# ADSR_Schematic.net
KiCad netlist of a schematic drawn in Altium Designer
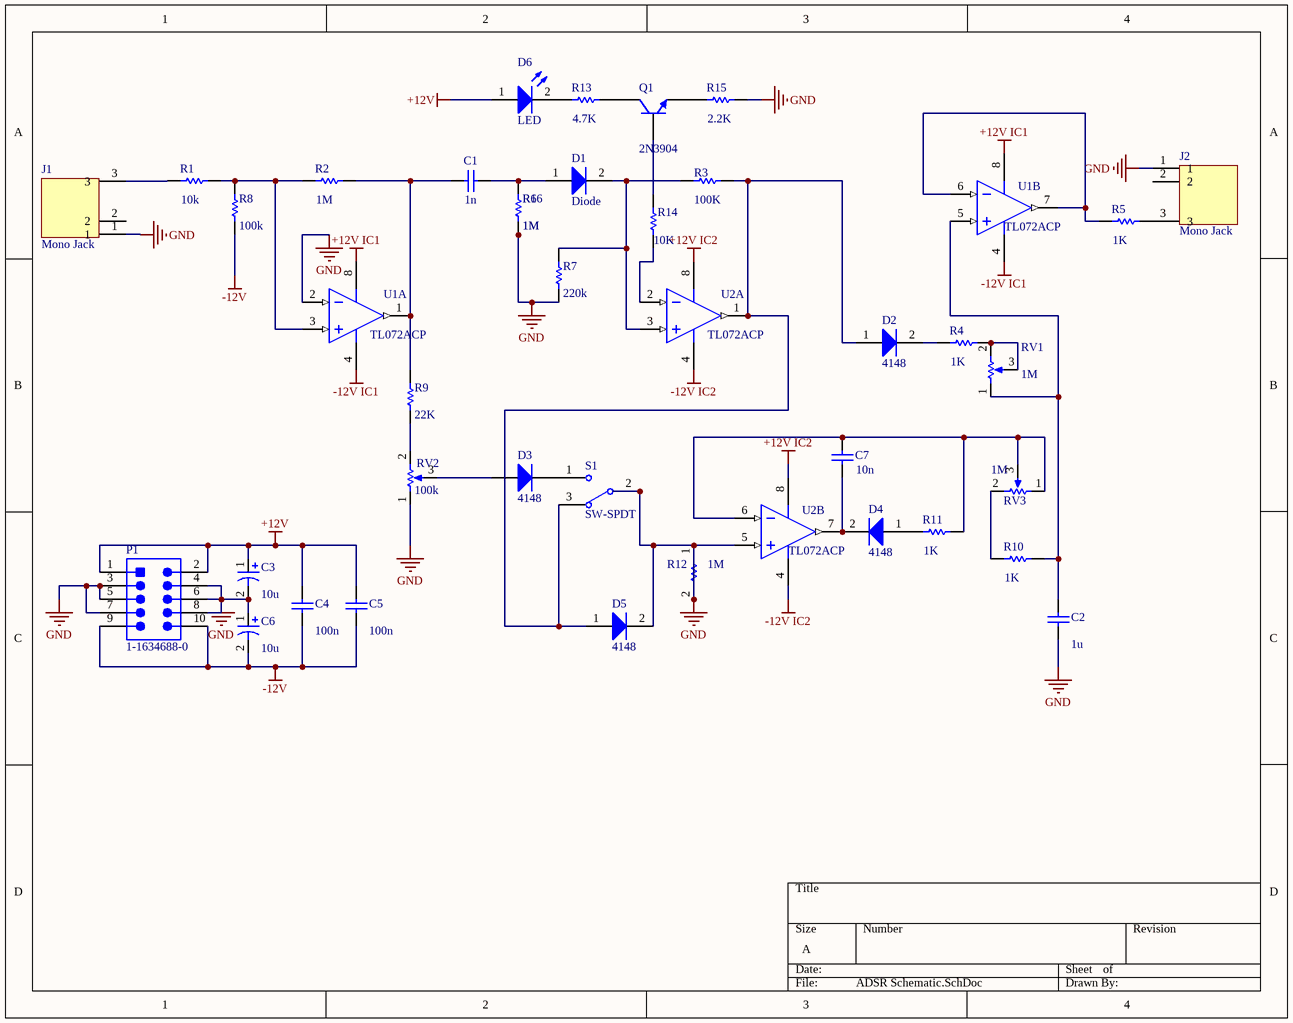
[diagram p0: ADSR Schematic.SchDoc]

(export (version "E")
  (design (tool "Eeschema 10.0.6"))
  (components
    (comp (ref "C1")
      (value "1n")
      (footprint "Ceramic_Cap")
      (description "Capacitor")
      (fields (field (name "Comment") "Cap") (field (name "PUBLISHER") "Altium Limited"))
      (libsource (lib "Miscellaneous Devices") (part "Cap"))
    )
    (comp (ref "C2")
      (value "1u")
      (footprint "Ceramic_Cap")
      (description "Capacitor")
      (fields (field (name "Comment") "Cap") (field (name "PUBLISHER") "Altium Limited"))
      (libsource (lib "Miscellaneous Devices") (part "Cap"))
    )
    (comp (ref "C3")
      (value "10u")
      (footprint "Electrolytic_Cap")
      (description "Polarized Capacitor (Radial)")
      (fields (field (name "Comment") "Cap Pol1") (field (name "PUBLISHER") "Altium Limited"))
      (libsource (lib "Miscellaneous Devices") (part "Cap Pol1"))
    )
    (comp (ref "C4")
      (value "100n")
      (footprint "Ceramic_Cap")
      (description "Capacitor")
      (fields (field (name "Comment") "Cap") (field (name "PUBLISHER") "Altium Limited"))
      (libsource (lib "Miscellaneous Devices") (part "Cap"))
    )
    (comp (ref "C5")
      (value "100n")
      (footprint "Ceramic_Cap")
      (description "Capacitor")
      (fields (field (name "Comment") "Cap") (field (name "PUBLISHER") "Altium Limited"))
      (libsource (lib "Miscellaneous Devices") (part "Cap"))
    )
    (comp (ref "C6")
      (value "10u")
      (footprint "Electrolytic_Cap")
      (description "Polarized Capacitor (Radial)")
      (fields (field (name "Comment") "Cap Pol1") (field (name "PUBLISHER") "Altium Limited"))
      (libsource (lib "Miscellaneous Devices") (part "Cap Pol1"))
    )
    (comp (ref "C7")
      (value "10n")
      (footprint "Ceramic_Cap")
      (description "Capacitor")
      (fields (field (name "Comment") "Cap") (field (name "PUBLISHER") "Altium Limited"))
      (libsource (lib "Miscellaneous Devices") (part "Cap"))
    )
    (comp (ref "D1")
      (value "Diode")
      (footprint "DIODE")
      (description "Default Diode")
      (fields (field (name "PUBLISHER") "Altium Limited"))
      (libsource (lib "Miscellaneous Devices") (part "Diode"))
    )
    (comp (ref "D2")
      (value "4148")
      (footprint "DIODE")
      (description "Default Diode")
      (fields (field (name "PUBLISHER") "Altium Limited"))
      (libsource (lib "Miscellaneous Devices") (part "Diode"))
    )
    (comp (ref "D3")
      (value "4148")
      (footprint "DIODE")
      (description "Default Diode")
      (fields (field (name "PUBLISHER") "Altium Limited"))
      (libsource (lib "") (part "Diode_1"))
    )
    (comp (ref "D4")
      (value "4148")
      (footprint "DIODE")
      (description "Default Diode")
      (fields (field (name "PUBLISHER") "Altium Limited"))
      (libsource (lib "Miscellaneous Devices") (part "Diode"))
    )
    (comp (ref "D5")
      (value "4148")
      (footprint "DIODE")
      (description "Default Diode")
      (fields (field (name "PUBLISHER") "Altium Limited"))
      (libsource (lib "Miscellaneous Devices") (part "Diode"))
    )
    (comp (ref "D6")
      (value "LED")
      (footprint "DIODE")
      (description "Typical INFRARED GaAs LED")
      (fields (field (name "PUBLISHER") "Altium Limited"))
      (libsource (lib "Miscellaneous Devices") (part "LED0"))
    )
    (comp (ref "J1")
      (value "Mono Jack")
      (footprint "MONO_Jack")
      (description "Phone Connectors Audio Socket 3.5MM 2P SCR")
      (fields (field (name "MANUFACTURER") "Schurter") (field (name "MANUFACTURER PART NUMBER") "4832.2211"))
      (libsource (lib "Schlib1") (part "4832.2211"))
    )
    (comp (ref "J2")
      (value "Mono Jack")
      (footprint "MONO_Jack")
      (description "Phone Connectors Audio Socket 3.5MM 2P SCR")
      (fields (field (name "MANUFACTURER") "Schurter") (field (name "MANUFACTURER PART NUMBER") "4832.2211"))
      (libsource (lib "") (part "4832.2211_1"))
    )
    (comp (ref "P1")
      (value "1-1634688-0")
      (footprint "TECO-1-1634688-0-10_V")
      (fields (field (name "MANUFACTURER") "TE Connectivity"))
      (libsource (lib "Altium Content Vault") (part "CN-2P-M-R10"))
    )
    (comp (ref "Q1")
      (value "2N3904")
      (footprint "TO-92A")
      (description "NPN General Purpose Amplifier")
      (fields (field (name "PUBLISHER") "Altium Limited"))
      (libsource (lib "Miscellaneous Devices") (part "2N3904"))
    )
    (comp (ref "R1")
      (value "10k")
      (footprint "R_SMT")
      (description "Resistor")
      (fields (field (name "Comment") "Res1") (field (name "PUBLISHER") "Altium Limited"))
      (libsource (lib "Miscellaneous Devices") (part "Res1"))
    )
    (comp (ref "R2")
      (value "1M")
      (footprint "R_SMT")
      (description "Resistor")
      (fields (field (name "Comment") "Res1") (field (name "PUBLISHER") "Altium Limited"))
      (libsource (lib "Miscellaneous Devices") (part "Res1"))
    )
    (comp (ref "R3")
      (value "100K")
      (footprint "R_SMT")
      (description "Resistor")
      (fields (field (name "Comment") "Res1") (field (name "PUBLISHER") "Altium Limited"))
      (libsource (lib "Miscellaneous Devices") (part "Res1"))
    )
    (comp (ref "R4")
      (value "1K")
      (footprint "R_SMT")
      (description "Resistor")
      (fields (field (name "Comment") "Res1") (field (name "PUBLISHER") "Altium Limited"))
      (libsource (lib "Miscellaneous Devices") (part "Res1"))
    )
    (comp (ref "R5")
      (value "1K")
      (footprint "R_SMT")
      (description "Resistor")
      (fields (field (name "Comment") "Res1") (field (name "PUBLISHER") "Altium Limited"))
      (libsource (lib "Miscellaneous Devices") (part "Res1"))
    )
    (comp (ref "R6")
      (value "1M")
      (footprint "AXIAL-0.3")
      (description "Resistor")
      (fields (field (name "Comment") "Res1") (field (name "PUBLISHER") "Altium Limited"))
      (libsource (lib "Miscellaneous Devices") (part "Res1"))
    )
    (comp (ref "R7")
      (value "220k")
      (footprint "R_SMT")
      (description "Resistor")
      (fields (field (name "Comment") "Res1") (field (name "PUBLISHER") "Altium Limited"))
      (libsource (lib "Miscellaneous Devices") (part "Res1"))
    )
    (comp (ref "R8")
      (value "100k")
      (footprint "R_SMT")
      (description "Resistor")
      (fields (field (name "Comment") "Res1") (field (name "PUBLISHER") "Altium Limited"))
      (libsource (lib "Miscellaneous Devices") (part "Res1"))
    )
    (comp (ref "R9")
      (value "22K")
      (footprint "R_SMT")
      (description "Resistor")
      (fields (field (name "Comment") "Res1") (field (name "PUBLISHER") "Altium Limited"))
      (libsource (lib "Miscellaneous Devices") (part "Res1"))
    )
    (comp (ref "R10")
      (value "1K")
      (footprint "R_SMT")
      (description "Resistor")
      (fields (field (name "Comment") "Res1") (field (name "PUBLISHER") "Altium Limited"))
      (libsource (lib "Miscellaneous Devices") (part "Res1"))
    )
    (comp (ref "R11")
      (value "1K")
      (footprint "R_SMT")
      (description "Resistor")
      (fields (field (name "Comment") "Res1") (field (name "PUBLISHER") "Altium Limited"))
      (libsource (lib "Miscellaneous Devices") (part "Res1"))
    )
    (comp (ref "R12")
      (value "1M")
      (footprint "R_SMT")
      (description "Resistor")
      (fields (field (name "Comment") "Res1") (field (name "PUBLISHER") "Altium Limited"))
      (libsource (lib "") (part "Res1_1"))
    )
    (comp (ref "R13")
      (value "4.7K")
      (footprint "R_SMT")
      (description "Resistor")
      (fields (field (name "Comment") "Res1") (field (name "PUBLISHER") "Altium Limited"))
      (libsource (lib "Miscellaneous Devices") (part "Res1"))
    )
    (comp (ref "R14")
      (value "10K")
      (footprint "R_SMT")
      (description "Resistor")
      (fields (field (name "Comment") "Res1") (field (name "PUBLISHER") "Altium Limited"))
      (libsource (lib "Miscellaneous Devices") (part "Res1"))
    )
    (comp (ref "R15")
      (value "2.2K")
      (footprint "R_SMT")
      (description "Resistor")
      (fields (field (name "Comment") "Res1") (field (name "PUBLISHER") "Altium Limited"))
      (libsource (lib "Miscellaneous Devices") (part "Res1"))
    )
    (comp (ref "R16")
      (value "1M")
      (footprint "R_SMT")
      (description "Resistor")
      (fields (field (name "Comment") "Res1") (field (name "PUBLISHER") "Altium Limited"))
      (libsource (lib "Miscellaneous Devices") (part "Res1"))
    )
    (comp (ref "RV1")
      (value "1M")
      (footprint "POT")
      (description "Potentiometer")
      (fields (field (name "Comment") "RPot") (field (name "PUBLISHER") "Altium Limited"))
      (libsource (lib "Miscellaneous Devices") (part "RPot"))
    )
    (comp (ref "RV2")
      (value "100k")
      (footprint "POT")
      (description "Potentiometer")
      (fields (field (name "Comment") "RPot") (field (name "PUBLISHER") "Altium Limited"))
      (libsource (lib "Miscellaneous Devices") (part "RPot"))
    )
    (comp (ref "RV3")
      (value "1M")
      (footprint "POT")
      (description "Potentiometer")
      (fields (field (name "Comment") "RPot") (field (name "PUBLISHER") "Altium Limited"))
      (libsource (lib "Miscellaneous Devices") (part "RPot"))
    )
    (comp (ref "S1")
      (value "SW-SPDT")
      (footprint "TL36WW15050")
      (description "SPDT Subminiature Toggle Switch, Right Angle Mounting, Vertical Actuation")
      (fields (field (name "PUBLISHER") "Altium Limited"))
      (libsource (lib "Miscellaneous Devices") (part "SW-SPDT"))
    )
    (comp (ref "U1")
      (value "TL072ACP")
      (footprint "P0008A")
      (fields (field (name "MANUFACTURER") "Texas Instruments"))
      (libsource (lib "Schlib1") (part "TI-AMP-D6-2-8_D"))
    )
    (comp (ref "U2")
      (value "TL072ACP")
      (footprint "P0008A")
      (fields (field (name "MANUFACTURER") "Texas Instruments"))
      (libsource (lib "Altium Content Vault") (part "TI-AMP-D6-2-8_D"))
    )
  )
  (nets
    (net (code "1") (name "+12V") (class "Default")
      (node (ref "C3") (pin "1") (pinfunction "1_1") (pintype "passive"))
      (node (ref "C4") (pin "1") (pinfunction "1_1") (pintype "passive"))
      (node (ref "C5") (pin "1") (pinfunction "1_1") (pintype "passive"))
      (node (ref "D6") (pin "1") (pinfunction "A_1") (pintype "passive"))
      (node (ref "P1") (pin "1") (pinfunction "1_1") (pintype "passive"))
      (node (ref "P1") (pin "2") (pinfunction "2_2") (pintype "passive"))
    )
    (net (code "2") (name "+12V IC1") (class "Default")
      (node (ref "U1") (pin "8") (pinfunction "VCC+_8") (pintype "power_in"))
    )
    (net (code "3") (name "+12V IC2") (class "Default")
      (node (ref "U2") (pin "8") (pinfunction "VCC+_8") (pintype "power_in"))
    )
    (net (code "4") (name "-12V") (class "Default")
      (node (ref "C4") (pin "2") (pinfunction "2_2") (pintype "passive"))
      (node (ref "C5") (pin "2") (pinfunction "2_2") (pintype "passive"))
      (node (ref "C6") (pin "2") (pinfunction "2_2") (pintype "passive"))
      (node (ref "P1") (pin "10") (pinfunction "10_10") (pintype "passive"))
      (node (ref "P1") (pin "9") (pinfunction "9_9") (pintype "passive"))
      (node (ref "R8") (pin "1") (pinfunction "1_1") (pintype "passive"))
    )
    (net (code "5") (name "-12V IC1") (class "Default")
      (node (ref "U1") (pin "4") (pinfunction "VCC-_4") (pintype "power_in"))
    )
    (net (code "6") (name "-12V IC2") (class "Default")
      (node (ref "U2") (pin "4") (pinfunction "VCC-_4") (pintype "power_in"))
    )
    (net (code "7") (name "GND") (class "Default")
      (node (ref "C2") (pin "2") (pinfunction "2_2") (pintype "passive"))
      (node (ref "C3") (pin "2") (pinfunction "2_2") (pintype "passive"))
      (node (ref "C6") (pin "1") (pinfunction "1_1") (pintype "passive"))
      (node (ref "D5") (pin "2") (pinfunction "K_2") (pintype "passive"))
      (node (ref "J1") (pin "1") (pinfunction "1_1") (pintype "passive"))
      (node (ref "J2") (pin "1") (pinfunction "1_1") (pintype "passive"))
      (node (ref "P1") (pin "3") (pinfunction "3_3") (pintype "passive"))
      (node (ref "P1") (pin "4") (pinfunction "4_4") (pintype "passive"))
      (node (ref "P1") (pin "5") (pinfunction "5_5") (pintype "passive"))
      (node (ref "P1") (pin "6") (pinfunction "6_6") (pintype "passive"))
      (node (ref "P1") (pin "7") (pinfunction "7_7") (pintype "passive"))
      (node (ref "P1") (pin "8") (pinfunction "8_8") (pintype "passive"))
      (node (ref "R12") (pin "1") (pinfunction "1_1") (pintype "passive"))
      (node (ref "R12") (pin "2") (pinfunction "2_2") (pintype "passive"))
      (node (ref "R15") (pin "2") (pinfunction "2_2") (pintype "passive"))
      (node (ref "R16") (pin "2") (pinfunction "2_2") (pintype "passive"))
      (node (ref "R6") (pin "2") (pinfunction "2_2") (pintype "passive"))
      (node (ref "R7") (pin "1") (pinfunction "1_1") (pintype "passive"))
      (node (ref "RV2") (pin "1") (pinfunction "TOP_1") (pintype "passive"))
      (node (ref "S1") (pin "2") (pinfunction "2_2") (pintype "passive"))
      (node (ref "U1") (pin "2") (pinfunction "IN1-_2") (pintype "input"))
      (node (ref "U2") (pin "5") (pinfunction "IN2+_5") (pintype "input"))
    )
    (net (code "8") (name "Net-(D1-A)") (class "Default")
      (node (ref "C1") (pin "2") (pinfunction "2_2") (pintype "passive"))
      (node (ref "D1") (pin "1") (pinfunction "A_1") (pintype "passive"))
      (node (ref "R16") (pin "1") (pinfunction "1_1") (pintype "passive"))
      (node (ref "R6") (pin "1") (pinfunction "1_1") (pintype "passive"))
    )
    (net (code "9") (name "Net-(D1-K)") (class "Default")
      (node (ref "D1") (pin "2") (pinfunction "K_2") (pintype "passive"))
      (node (ref "R3") (pin "2") (pinfunction "2_2") (pintype "passive"))
      (node (ref "R7") (pin "2") (pinfunction "2_2") (pintype "passive"))
      (node (ref "U2") (pin "3") (pinfunction "IN1+_3") (pintype "input"))
    )
    (net (code "10") (name "Net-(D2-A)") (class "Default")
      (node (ref "D2") (pin "1") (pinfunction "A_1") (pintype "passive"))
      (node (ref "D5") (pin "1") (pinfunction "A_1") (pintype "passive"))
      (node (ref "R3") (pin "1") (pinfunction "1_1") (pintype "passive"))
      (node (ref "S1") (pin "3") (pinfunction "3_3") (pintype "passive"))
      (node (ref "U2") (pin "1") (pinfunction "OUT1_1") (pintype "output"))
    )
    (net (code "11") (name "Net-(D2-K)") (class "Default")
      (node (ref "D2") (pin "2") (pinfunction "K_2") (pintype "passive"))
      (node (ref "R4") (pin "2") (pinfunction "2_2") (pintype "passive"))
    )
    (net (code "12") (name "Net-(D3-A)") (class "Default")
      (node (ref "D3") (pin "1") (pinfunction "A_1") (pintype "passive"))
      (node (ref "RV2") (pin "3") (pinfunction "TAP_3") (pintype "passive"))
    )
    (net (code "13") (name "Net-(D3-K)") (class "Default")
      (node (ref "D3") (pin "2") (pinfunction "K_2") (pintype "passive"))
      (node (ref "S1") (pin "1") (pinfunction "1_1") (pintype "passive"))
    )
    (net (code "14") (name "Net-(D4-A)") (class "Default")
      (node (ref "D4") (pin "1") (pinfunction "A_1") (pintype "passive"))
      (node (ref "R11") (pin "1") (pinfunction "1_1") (pintype "passive"))
    )
    (net (code "15") (name "Net-(D4-K)") (class "Default")
      (node (ref "C7") (pin "1") (pinfunction "1_1") (pintype "passive"))
      (node (ref "D4") (pin "2") (pinfunction "K_2") (pintype "passive"))
      (node (ref "U2") (pin "7") (pinfunction "OUT2_7") (pintype "output"))
    )
    (net (code "16") (name "Net-(D6-K)") (class "Default")
      (node (ref "D6") (pin "2") (pinfunction "K_2") (pintype "passive"))
      (node (ref "R13") (pin "1") (pinfunction "1_1") (pintype "passive"))
    )
    (net (code "17") (name "Net-(J1-Pad3)") (class "Default")
      (node (ref "J1") (pin "3") (pinfunction "3_3") (pintype "passive"))
      (node (ref "R1") (pin "1") (pinfunction "1_1") (pintype "passive"))
    )
    (net (code "18") (name "Net-(J2-Pad3)") (class "Default")
      (node (ref "J2") (pin "3") (pinfunction "3_3") (pintype "passive"))
      (node (ref "R5") (pin "2") (pinfunction "2_2") (pintype "passive"))
    )
    (net (code "19") (name "Net-(Q1-B)") (class "Default")
      (node (ref "Q1") (pin "2") (pinfunction "B_2") (pintype "passive"))
      (node (ref "R14") (pin "1") (pinfunction "1_1") (pintype "passive"))
    )
    (net (code "20") (name "Net-(Q1-C)") (class "Default")
      (node (ref "Q1") (pin "3") (pinfunction "C_3") (pintype "passive"))
      (node (ref "R13") (pin "2") (pinfunction "2_2") (pintype "passive"))
    )
    (net (code "21") (name "Net-(Q1-E)") (class "Default")
      (node (ref "Q1") (pin "1") (pinfunction "E_1") (pintype "passive"))
      (node (ref "R15") (pin "1") (pinfunction "1_1") (pintype "passive"))
    )
    (net (code "22") (name "Net-(RV1-BOT)") (class "Default")
      (node (ref "R4") (pin "1") (pinfunction "1_1") (pintype "passive"))
      (node (ref "RV1") (pin "2") (pinfunction "BOT_2") (pintype "passive"))
      (node (ref "RV1") (pin "3") (pinfunction "TAP_3") (pintype "passive"))
    )
    (net (code "23") (name "Net-(RV1-TOP)") (class "Default")
      (node (ref "C2") (pin "1") (pinfunction "1_1") (pintype "passive"))
      (node (ref "R10") (pin "2") (pinfunction "2_2") (pintype "passive"))
      (node (ref "RV1") (pin "1") (pinfunction "TOP_1") (pintype "passive"))
      (node (ref "U1") (pin "5") (pinfunction "IN2+_5") (pintype "input"))
    )
    (net (code "24") (name "Net-(RV2-BOT)") (class "Default")
      (node (ref "R9") (pin "2") (pinfunction "2_2") (pintype "passive"))
      (node (ref "RV2") (pin "2") (pinfunction "BOT_2") (pintype "passive"))
    )
    (net (code "25") (name "Net-(RV3-BOT)") (class "Default")
      (node (ref "R10") (pin "1") (pinfunction "1_1") (pintype "passive"))
      (node (ref "RV3") (pin "2") (pinfunction "BOT_2") (pintype "passive"))
    )
    (net (code "26") (name "Net-(RV3-TAP)") (class "Default")
      (node (ref "C7") (pin "2") (pinfunction "2_2") (pintype "passive"))
      (node (ref "R11") (pin "2") (pinfunction "2_2") (pintype "passive"))
      (node (ref "RV3") (pin "1") (pinfunction "TOP_1") (pintype "passive"))
      (node (ref "RV3") (pin "3") (pinfunction "TAP_3") (pintype "passive"))
      (node (ref "U2") (pin "6") (pinfunction "IN2-_6") (pintype "input"))
    )
    (net (code "27") (name "Net-(U1A-IN1+)") (class "Default")
      (node (ref "R1") (pin "2") (pinfunction "2_2") (pintype "passive"))
      (node (ref "R2") (pin "1") (pinfunction "1_1") (pintype "passive"))
      (node (ref "R8") (pin "2") (pinfunction "2_2") (pintype "passive"))
      (node (ref "U1") (pin "3") (pinfunction "IN1+_3") (pintype "input"))
    )
    (net (code "28") (name "Net-(U1A-OUT1)") (class "Default")
      (node (ref "C1") (pin "1") (pinfunction "1_1") (pintype "passive"))
      (node (ref "R2") (pin "2") (pinfunction "2_2") (pintype "passive"))
      (node (ref "R9") (pin "1") (pinfunction "1_1") (pintype "passive"))
      (node (ref "U1") (pin "1") (pinfunction "OUT1_1") (pintype "output"))
    )
    (net (code "29") (name "Net-(U1B-IN2-)") (class "Default")
      (node (ref "R5") (pin "1") (pinfunction "1_1") (pintype "passive"))
      (node (ref "U1") (pin "6") (pinfunction "IN2-_6") (pintype "input"))
      (node (ref "U1") (pin "7") (pinfunction "OUT2_7") (pintype "output"))
    )
    (net (code "30") (name "Net-(U2A-IN1-)") (class "Default")
      (node (ref "R14") (pin "2") (pinfunction "2_2") (pintype "passive"))
      (node (ref "U2") (pin "2") (pinfunction "IN1-_2") (pintype "input"))
    )
    (net (code "31") (name "unconnected-(J1-Pad2)") (class "Default")
      (node (ref "J1") (pin "2") (pinfunction "2_2") (pintype "passive"))
    )
    (net (code "32") (name "unconnected-(J2-Pad2)") (class "Default")
      (node (ref "J2") (pin "2") (pinfunction "2_2") (pintype "passive"))
    )
  )
)
